# magicmouth-v1_0.net
KiCad netlist of a schematic drawn in EAGLE
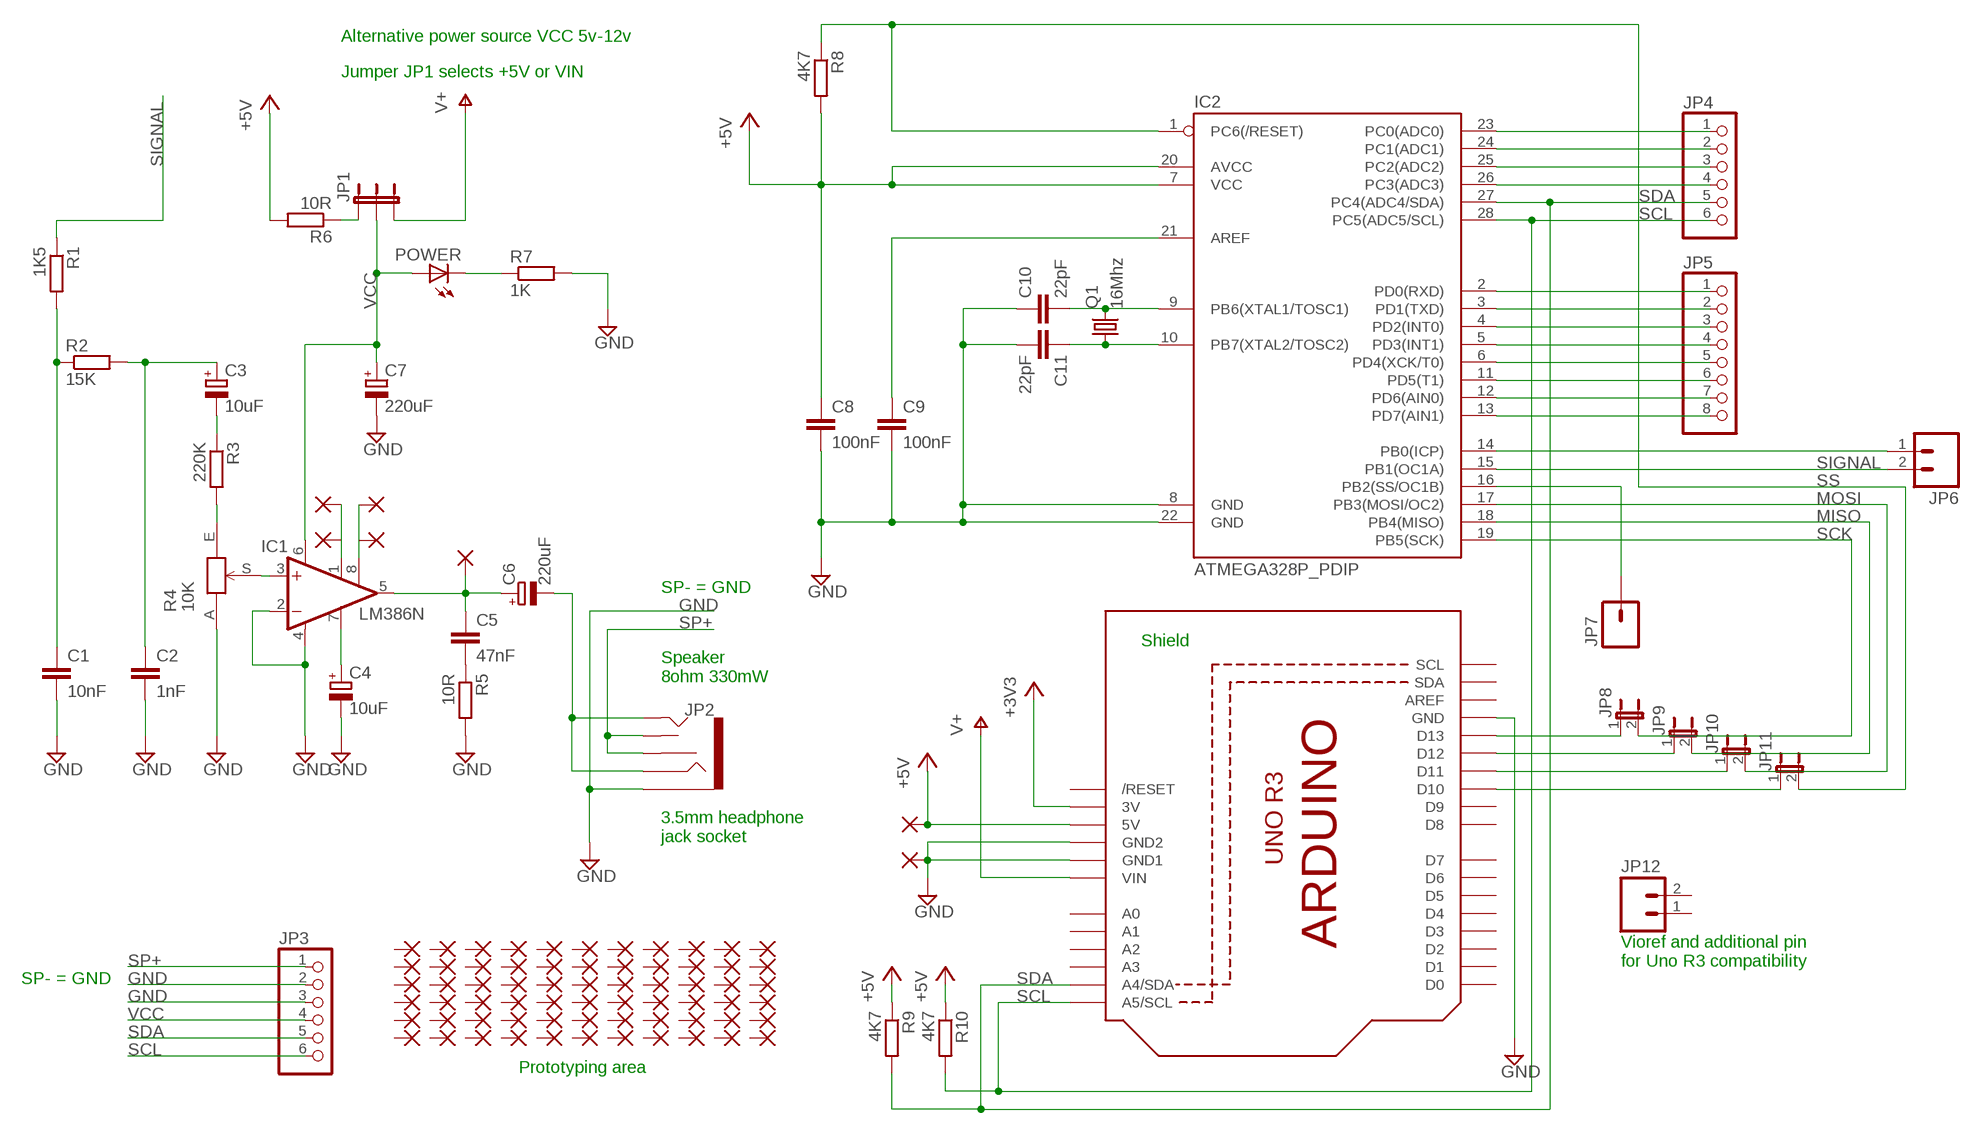
[diagram p0: schematic, sheet 1]

(export (version "E")
  (design (tool "Eeschema 10.0.6"))
  (components
    (comp (ref "C1")
      (value "10nF")
      (footprint "eagle-import:C050-025X075")
      (libsource (lib "eagle-import") (part "C-EU050-025X075"))
    )
    (comp (ref "C2")
      (value "1nF")
      (footprint "eagle-import:C050-025X075")
      (libsource (lib "eagle-import") (part "C-EU050-025X075"))
    )
    (comp (ref "C3")
      (value "10uF")
      (footprint "eagle-import:E2,5-7")
      (libsource (lib "eagle-import") (part "CPOL-EUE2.5-7"))
    )
    (comp (ref "C4")
      (value "10uF")
      (footprint "eagle-import:E2,5-7")
      (libsource (lib "eagle-import") (part "CPOL-EUE2.5-7"))
    )
    (comp (ref "C5")
      (value "47nF")
      (footprint "eagle-import:C050-025X075")
      (libsource (lib "eagle-import") (part "C-EU050-025X075"))
    )
    (comp (ref "C6")
      (value "220uF")
      (footprint "eagle-import:TT2D7")
      (libsource (lib "eagle-import") (part "CPOL-EUTT2D7"))
    )
    (comp (ref "C7")
      (value "220uF")
      (footprint "eagle-import:TT2D7")
      (libsource (lib "eagle-import") (part "CPOL-EUTT2D7"))
    )
    (comp (ref "C8")
      (value "100nF")
      (footprint "eagle-import:C025-025X050")
      (fields (field (name "CAPACITANCE") "10 nF"))
      (libsource (lib "eagle-import") (part "C-EU025-025X050"))
    )
    (comp (ref "C9")
      (value "100nF")
      (footprint "eagle-import:C025-025X050")
      (fields (field (name "CAPACITANCE") "100 nF"))
      (libsource (lib "eagle-import") (part "C-EU025-025X050"))
    )
    (comp (ref "C10")
      (value "22pF")
      (footprint "eagle-import:C025-025X050")
      (fields (field (name "CAPACITANCE") "22 pf"))
      (libsource (lib "eagle-import") (part "C-EU025-025X050"))
    )
    (comp (ref "C11")
      (value "22pF")
      (footprint "eagle-import:C025-025X050")
      (fields (field (name "CAPACITANCE") "22 pf"))
      (libsource (lib "eagle-import") (part "C-EU025-025X050"))
    )
    (comp (ref "IC1")
      (value "LM386N")
      (footprint "eagle-import:DIL08")
      (libsource (lib "eagle-import") (part "LM386?-N1"))
    )
    (comp (ref "IC2")
      (value "ATMEGA328P_PDIP")
      (footprint "eagle-import:DIL28-3")
      (libsource (lib "eagle-import") (part "ATMEGA328P_PDIP"))
    )
    (comp (ref "JP1")
      (value "JUMPER-3PTH")
      (footprint "eagle-import:1X03")
      (libsource (lib "eagle-import") (part "JUMPER-3PTH"))
    )
    (comp (ref "JP2")
      (value "AUDIO-JACK2PTH")
      (footprint "eagle-import:AUDIO-JACK")
      (libsource (lib "eagle-import") (part "AUDIO-JACK2PTH"))
    )
    (comp (ref "JP3")
      (value "PINHD-1X6CB")
      (footprint "eagle-import:1X06-CLEANBIG")
      (libsource (lib "eagle-import") (part "PINHD-1X6CB"))
    )
    (comp (ref "JP4")
      (value "PINHD-1X6CB")
      (footprint "eagle-import:1X06-CLEANBIG")
      (libsource (lib "eagle-import") (part "PINHD-1X6CB"))
    )
    (comp (ref "JP5")
      (value "PINHD-1X8CLEANBIG")
      (footprint "eagle-import:1X08-CLEANBIG")
      (libsource (lib "eagle-import") (part "PINHD-1X8CLEANBIG"))
    )
    (comp (ref "JP6")
      (value "M021X02_NO_SILK")
      (footprint "eagle-import:1X02_NO_SILK")
      (libsource (lib "eagle-import") (part "SparkFun-Connectors_M021X02_NO_SILK"))
    )
    (comp (ref "JP7")
      (value "M01SMDNS")
      (footprint "eagle-import:1X01NS")
      (libsource (lib "eagle-import") (part "M01SMDNS"))
    )
    (comp (ref "JP8")
      (value "JUMPER-2PTH")
      (footprint "eagle-import:1X02")
      (libsource (lib "eagle-import") (part "JUMPER-2PTH"))
    )
    (comp (ref "JP9")
      (value "JUMPER-2PTH")
      (footprint "eagle-import:1X02")
      (libsource (lib "eagle-import") (part "JUMPER-2PTH"))
    )
    (comp (ref "JP10")
      (value "JUMPER-2PTH")
      (footprint "eagle-import:1X02")
      (libsource (lib "eagle-import") (part "JUMPER-2PTH"))
    )
    (comp (ref "JP11")
      (value "JUMPER-2PTH")
      (footprint "eagle-import:1X02")
      (libsource (lib "eagle-import") (part "JUMPER-2PTH"))
    )
    (comp (ref "JP12")
      (value "M021X02_NO_SILK")
      (footprint "eagle-import:1X02_NO_SILK")
      (libsource (lib "eagle-import") (part "M021X02_NO_SILK"))
    )
    (comp (ref "P1")
      (value "1,6/0,8")
      (footprint "eagle-import:1,6_0,8")
      (libsource (lib "eagle-import") (part "1,6/0,8"))
    )
    (comp (ref "P5")
      (value "1,6/0,8")
      (footprint "eagle-import:1,6_0,8")
      (libsource (lib "eagle-import") (part "1,6/0,8"))
    )
    (comp (ref "P8")
      (value "1,6/0,8")
      (footprint "eagle-import:1,6_0,8")
      (libsource (lib "eagle-import") (part "1,6/0,8"))
    )
    (comp (ref "PAD1")
      (value "1,6/0,8")
      (footprint "eagle-import:1,6_0,8")
      (libsource (lib "eagle-import") (part "1,6/0,8"))
    )
    (comp (ref "PAD3")
      (value "1,6/0,8")
      (footprint "eagle-import:1,6_0,8")
      (libsource (lib "eagle-import") (part "1,6/0,8"))
    )
    (comp (ref "PAD7")
      (value "1,6/0,8")
      (footprint "eagle-import:1,6_0,8")
      (libsource (lib "eagle-import") (part "1,6/0,8"))
    )
    (comp (ref "PAD8")
      (value "1,6/0,8")
      (footprint "eagle-import:1,6_0,8")
      (libsource (lib "eagle-import") (part "1,6/0,8"))
    )
    (comp (ref "PAD9")
      (value "1,6/0,8")
      (footprint "eagle-import:1,6_0,8")
      (libsource (lib "eagle-import") (part "1,6/0,8"))
    )
    (comp (ref "PAD10")
      (value "1,6/0,8")
      (footprint "eagle-import:1,6_0,8")
      (libsource (lib "eagle-import") (part "1,6/0,8"))
    )
    (comp (ref "PAD11")
      (value "1,6/0,8")
      (footprint "eagle-import:1,6_0,8")
      (libsource (lib "eagle-import") (part "1,6/0,8"))
    )
    (comp (ref "PAD12")
      (value "1,6/0,8")
      (footprint "eagle-import:1,6_0,8")
      (libsource (lib "eagle-import") (part "1,6/0,8"))
    )
    (comp (ref "PAD13")
      (value "1,6/0,8")
      (footprint "eagle-import:1,6_0,8")
      (libsource (lib "eagle-import") (part "1,6/0,8"))
    )
    (comp (ref "PAD14")
      (value "1,6/0,8")
      (footprint "eagle-import:1,6_0,8")
      (libsource (lib "eagle-import") (part "1,6/0,8"))
    )
    (comp (ref "PAD15")
      (value "1,6/0,8")
      (footprint "eagle-import:1,6_0,8")
      (libsource (lib "eagle-import") (part "1,6/0,8"))
    )
    (comp (ref "PAD16")
      (value "1,6/0,8")
      (footprint "eagle-import:1,6_0,8")
      (libsource (lib "eagle-import") (part "1,6/0,8"))
    )
    (comp (ref "PAD17")
      (value "1,6/0,8")
      (footprint "eagle-import:1,6_0,8")
      (libsource (lib "eagle-import") (part "1,6/0,8"))
    )
    (comp (ref "PAD18")
      (value "1,6/0,8")
      (footprint "eagle-import:1,6_0,8")
      (libsource (lib "eagle-import") (part "1,6/0,8"))
    )
    (comp (ref "PAD19")
      (value "1,6/0,8")
      (footprint "eagle-import:1,6_0,8")
      (libsource (lib "eagle-import") (part "1,6/0,8"))
    )
    (comp (ref "PAD20")
      (value "1,6/0,8")
      (footprint "eagle-import:1,6_0,8")
      (libsource (lib "eagle-import") (part "1,6/0,8"))
    )
    (comp (ref "PAD21")
      (value "1,6/0,8")
      (footprint "eagle-import:1,6_0,8")
      (libsource (lib "eagle-import") (part "1,6/0,8"))
    )
    (comp (ref "PAD22")
      (value "1,6/0,8")
      (footprint "eagle-import:1,6_0,8")
      (libsource (lib "eagle-import") (part "1,6/0,8"))
    )
    (comp (ref "PAD23")
      (value "1,6/0,8")
      (footprint "eagle-import:1,6_0,8")
      (libsource (lib "eagle-import") (part "1,6/0,8"))
    )
    (comp (ref "PAD24")
      (value "1,6/0,8")
      (footprint "eagle-import:1,6_0,8")
      (libsource (lib "eagle-import") (part "1,6/0,8"))
    )
    (comp (ref "PAD25")
      (value "1,6/0,8")
      (footprint "eagle-import:1,6_0,8")
      (libsource (lib "eagle-import") (part "1,6/0,8"))
    )
    (comp (ref "PAD26")
      (value "1,6/0,8")
      (footprint "eagle-import:1,6_0,8")
      (libsource (lib "eagle-import") (part "1,6/0,8"))
    )
    (comp (ref "PAD27")
      (value "1,6/0,8")
      (footprint "eagle-import:1,6_0,8")
      (libsource (lib "eagle-import") (part "1,6/0,8"))
    )
    (comp (ref "PAD28")
      (value "1,6/0,8")
      (footprint "eagle-import:1,6_0,8")
      (libsource (lib "eagle-import") (part "1,6/0,8"))
    )
    (comp (ref "PAD29")
      (value "1,6/0,8")
      (footprint "eagle-import:1,6_0,8")
      (libsource (lib "eagle-import") (part "1,6/0,8"))
    )
    (comp (ref "PAD30")
      (value "1,6/0,8")
      (footprint "eagle-import:1,6_0,8")
      (libsource (lib "eagle-import") (part "1,6/0,8"))
    )
    (comp (ref "PAD31")
      (value "1,6/0,8")
      (footprint "eagle-import:1,6_0,8")
      (libsource (lib "eagle-import") (part "1,6/0,8"))
    )
    (comp (ref "PAD32")
      (value "1,6/0,8")
      (footprint "eagle-import:1,6_0,8")
      (libsource (lib "eagle-import") (part "1,6/0,8"))
    )
    (comp (ref "PAD33")
      (value "1,6/0,8")
      (footprint "eagle-import:1,6_0,8")
      (libsource (lib "eagle-import") (part "1,6/0,8"))
    )
    (comp (ref "PAD34")
      (value "1,6/0,8")
      (footprint "eagle-import:1,6_0,8")
      (libsource (lib "eagle-import") (part "1,6/0,8"))
    )
    (comp (ref "PAD35")
      (value "1,6/0,8")
      (footprint "eagle-import:1,6_0,8")
      (libsource (lib "eagle-import") (part "1,6/0,8"))
    )
    (comp (ref "PAD36")
      (value "1,6/0,8")
      (footprint "eagle-import:1,6_0,8")
      (libsource (lib "eagle-import") (part "1,6/0,8"))
    )
    (comp (ref "PAD37")
      (value "1,6/0,8")
      (footprint "eagle-import:1,6_0,8")
      (libsource (lib "eagle-import") (part "1,6/0,8"))
    )
    (comp (ref "PAD38")
      (value "1,6/0,8")
      (footprint "eagle-import:1,6_0,8")
      (libsource (lib "eagle-import") (part "1,6/0,8"))
    )
    (comp (ref "PAD39")
      (value "1,6/0,8")
      (footprint "eagle-import:1,6_0,8")
      (libsource (lib "eagle-import") (part "1,6/0,8"))
    )
    (comp (ref "PAD40")
      (value "1,6/0,8")
      (footprint "eagle-import:1,6_0,8")
      (libsource (lib "eagle-import") (part "1,6/0,8"))
    )
    (comp (ref "PAD41")
      (value "1,6/0,8")
      (footprint "eagle-import:1,6_0,8")
      (libsource (lib "eagle-import") (part "1,6/0,8"))
    )
    (comp (ref "PAD42")
      (value "1,6/0,8")
      (footprint "eagle-import:1,6_0,8")
      (libsource (lib "eagle-import") (part "1,6/0,8"))
    )
    (comp (ref "PAD43")
      (value "1,6/0,8")
      (footprint "eagle-import:1,6_0,8")
      (libsource (lib "eagle-import") (part "1,6/0,8"))
    )
    (comp (ref "PAD44")
      (value "1,6/0,8")
      (footprint "eagle-import:1,6_0,8")
      (libsource (lib "eagle-import") (part "1,6/0,8"))
    )
    (comp (ref "PAD45")
      (value "1,6/0,8")
      (footprint "eagle-import:1,6_0,8")
      (libsource (lib "eagle-import") (part "1,6/0,8"))
    )
    (comp (ref "PAD46")
      (value "1,6/0,8")
      (footprint "eagle-import:1,6_0,8")
      (libsource (lib "eagle-import") (part "1,6/0,8"))
    )
    (comp (ref "PAD47")
      (value "1,6/0,8")
      (footprint "eagle-import:1,6_0,8")
      (libsource (lib "eagle-import") (part "1,6/0,8"))
    )
    (comp (ref "PAD48")
      (value "1,6/0,8")
      (footprint "eagle-import:1,6_0,8")
      (libsource (lib "eagle-import") (part "1,6/0,8"))
    )
    (comp (ref "PAD49")
      (value "1,6/0,8")
      (footprint "eagle-import:1,6_0,8")
      (libsource (lib "eagle-import") (part "1,6/0,8"))
    )
    (comp (ref "PAD50")
      (value "1,6/0,8")
      (footprint "eagle-import:1,6_0,8")
      (libsource (lib "eagle-import") (part "1,6/0,8"))
    )
    (comp (ref "PAD51")
      (value "1,6/0,8")
      (footprint "eagle-import:1,6_0,8")
      (libsource (lib "eagle-import") (part "1,6/0,8"))
    )
    (comp (ref "PAD52")
      (value "1,6/0,8")
      (footprint "eagle-import:1,6_0,8")
      (libsource (lib "eagle-import") (part "1,6/0,8"))
    )
    (comp (ref "PAD53")
      (value "1,6/0,8")
      (footprint "eagle-import:1,6_0,8")
      (libsource (lib "eagle-import") (part "1,6/0,8"))
    )
    (comp (ref "PAD54")
      (value "1,6/0,8")
      (footprint "eagle-import:1,6_0,8")
      (libsource (lib "eagle-import") (part "1,6/0,8"))
    )
    (comp (ref "PAD55")
      (value "1,6/0,8")
      (footprint "eagle-import:1,6_0,8")
      (libsource (lib "eagle-import") (part "1,6/0,8"))
    )
    (comp (ref "PAD56")
      (value "1,6/0,8")
      (footprint "eagle-import:1,6_0,8")
      (libsource (lib "eagle-import") (part "1,6/0,8"))
    )
    (comp (ref "PAD57")
      (value "1,6/0,8")
      (footprint "eagle-import:1,6_0,8")
      (libsource (lib "eagle-import") (part "1,6/0,8"))
    )
    (comp (ref "PAD58")
      (value "1,6/0,8")
      (footprint "eagle-import:1,6_0,8")
      (libsource (lib "eagle-import") (part "1,6/0,8"))
    )
    (comp (ref "PAD59")
      (value "1,6/0,8")
      (footprint "eagle-import:1,6_0,8")
      (libsource (lib "eagle-import") (part "1,6/0,8"))
    )
    (comp (ref "PAD60")
      (value "1,6/0,8")
      (footprint "eagle-import:1,6_0,8")
      (libsource (lib "eagle-import") (part "1,6/0,8"))
    )
    (comp (ref "PAD61")
      (value "1,6/0,8")
      (footprint "eagle-import:1,6_0,8")
      (libsource (lib "eagle-import") (part "1,6/0,8"))
    )
    (comp (ref "PAD62")
      (value "1,6/0,8")
      (footprint "eagle-import:1,6_0,8")
      (libsource (lib "eagle-import") (part "1,6/0,8"))
    )
    (comp (ref "PAD63")
      (value "1,6/0,8")
      (footprint "eagle-import:1,6_0,8")
      (libsource (lib "eagle-import") (part "1,6/0,8"))
    )
    (comp (ref "PAD64")
      (value "1,6/0,8")
      (footprint "eagle-import:1,6_0,8")
      (libsource (lib "eagle-import") (part "1,6/0,8"))
    )
    (comp (ref "PAD65")
      (value "1,6/0,8")
      (footprint "eagle-import:1,6_0,8")
      (libsource (lib "eagle-import") (part "1,6/0,8"))
    )
    (comp (ref "PAD66")
      (value "1,6/0,8")
      (footprint "eagle-import:1,6_0,8")
      (libsource (lib "eagle-import") (part "1,6/0,8"))
    )
    (comp (ref "PAD67")
      (value "1,6/0,8")
      (footprint "eagle-import:1,6_0,8")
      (libsource (lib "eagle-import") (part "1,6/0,8"))
    )
    (comp (ref "PAD68")
      (value "1,6/0,8")
      (footprint "eagle-import:1,6_0,8")
      (libsource (lib "eagle-import") (part "1,6/0,8"))
    )
    (comp (ref "PAD69")
      (value "1,6/0,8")
      (footprint "eagle-import:1,6_0,8")
      (libsource (lib "eagle-import") (part "1,6/0,8"))
    )
    (comp (ref "PAD70")
      (value "1,6/0,8")
      (footprint "eagle-import:1,6_0,8")
      (libsource (lib "eagle-import") (part "1,6/0,8"))
    )
    (comp (ref "PAD71")
      (value "1,6/0,8")
      (footprint "eagle-import:1,6_0,8")
      (libsource (lib "eagle-import") (part "1,6/0,8"))
    )
    (comp (ref "PAD72")
      (value "1,6/0,8")
      (footprint "eagle-import:1,6_0,8")
      (libsource (lib "eagle-import") (part "1,6/0,8"))
    )
    (comp (ref "PAD73")
      (value "1,6/0,8")
      (footprint "eagle-import:1,6_0,8")
      (libsource (lib "eagle-import") (part "1,6/0,8"))
    )
    (comp (ref "PAD74")
      (value "1,6/0,8")
      (footprint "eagle-import:1,6_0,8")
      (libsource (lib "eagle-import") (part "1,6/0,8"))
    )
    (comp (ref "POWER")
      (value "LED3MM")
      (footprint "eagle-import:LED3MM")
      (libsource (lib "eagle-import") (part "LED3MM"))
    )
    (comp (ref "Q1")
      (value "16Mhz")
      (footprint "eagle-import:HC49_S")
      (libsource (lib "eagle-import") (part "CRYSTALHC49S"))
    )
    (comp (ref "R1")
      (value "1K5")
      (footprint "eagle-import:0207_7")
      (libsource (lib "eagle-import") (part "R-EU_0207/7"))
    )
    (comp (ref "R2")
      (value "15K")
      (footprint "eagle-import:0207_7")
      (libsource (lib "eagle-import") (part "R-EU_0207/7"))
    )
    (comp (ref "R3")
      (value "220K")
      (footprint "eagle-import:0207_7")
      (libsource (lib "eagle-import") (part "resistor_R-EU_0207/7"))
    )
    (comp (ref "R4")
      (value "10K")
      (footprint "eagle-import:3352T")
      (libsource (lib "eagle-import") (part "TPOT3352"))
    )
    (comp (ref "R5")
      (value "10R")
      (footprint "eagle-import:0207_7")
      (libsource (lib "eagle-import") (part "resistor_R-EU_0207/7"))
    )
    (comp (ref "R6")
      (value "10R")
      (footprint "eagle-import:0207_7")
      (libsource (lib "eagle-import") (part "R-EU_0207/7"))
    )
    (comp (ref "R7")
      (value "1K")
      (footprint "eagle-import:0207_7")
      (libsource (lib "eagle-import") (part "R-EU_0207/7"))
    )
    (comp (ref "R8")
      (value "4K7")
      (footprint "eagle-import:0207_7")
      (fields (field (name "RESISTANCE") "4K7"))
      (libsource (lib "eagle-import") (part "R-EU_0207/7"))
    )
    (comp (ref "R9")
      (value "4K7")
      (footprint "eagle-import:0207_7")
      (fields (field (name "RESISTANCE") "4K7"))
      (libsource (lib "eagle-import") (part "R-EU_0207/7"))
    )
    (comp (ref "R10")
      (value "4K7")
      (footprint "eagle-import:0207_7")
      (fields (field (name "RESISTANCE") "4K7"))
      (libsource (lib "eagle-import") (part "R-EU_0207/7"))
    )
    (comp (ref "U1")
      (value "ARDUINOR3-NOIOREF-NOTEXT")
      (footprint "eagle-import:ARDUINOR3-NOTEXT-NOIOREF")
      (libsource (lib "eagle-import") (part "ARDUINOR3-NOIOREF-NOTEXT"))
    )
  )
  (nets
    (net (code "1") (name "+3V3") (class "Default")
      (node (ref "U1") (pin "3V") (pinfunction "3V_3V") (pintype "power_in"))
    )
    (net (code "2") (name "+5V") (class "Default")
      (node (ref "C8") (pin "1") (pinfunction "1_1") (pintype "passive"))
      (node (ref "IC2") (pin "20") (pinfunction "AVCC_20") (pintype "bidirectional"))
      (node (ref "IC2") (pin "7") (pinfunction "VCC_7") (pintype "bidirectional"))
      (node (ref "PAD55") (pin "1") (pinfunction "P_1") (pintype "passive"))
      (node (ref "R10") (pin "1") (pinfunction "1_1") (pintype "passive"))
      (node (ref "R6") (pin "2") (pinfunction "2_2") (pintype "passive"))
      (node (ref "R8") (pin "2") (pinfunction "2_2") (pintype "passive"))
      (node (ref "R9") (pin "1") (pinfunction "1_1") (pintype "passive"))
      (node (ref "U1") (pin "5V") (pinfunction "5V_5V") (pintype "power_in"))
    )
    (net (code "3") (name "/MISO") (class "Default")
      (node (ref "IC2") (pin "18") (pinfunction "PB4(MISO)_18") (pintype "bidirectional"))
      (node (ref "JP9") (pin "2") (pinfunction "2_2") (pintype "passive"))
    )
    (net (code "4") (name "/MOSI") (class "Default")
      (node (ref "IC2") (pin "17") (pinfunction "PB3(MOSI/OC2)_17") (pintype "bidirectional"))
      (node (ref "JP10") (pin "2") (pinfunction "2_2") (pintype "passive"))
    )
    (net (code "5") (name "/SCK") (class "Default")
      (node (ref "IC2") (pin "19") (pinfunction "PB5(SCK)_19") (pintype "bidirectional"))
      (node (ref "JP8") (pin "2") (pinfunction "2_2") (pintype "passive"))
    )
    (net (code "6") (name "/SCL") (class "Default")
      (node (ref "IC2") (pin "28") (pinfunction "PC5(ADC5/SCL)_28") (pintype "bidirectional"))
      (node (ref "JP3") (pin "6") (pinfunction "6_6") (pintype "passive"))
      (node (ref "JP4") (pin "6") (pinfunction "6_6") (pintype "passive"))
      (node (ref "R10") (pin "2") (pinfunction "2_2") (pintype "passive"))
      (node (ref "U1") (pin "A5") (pinfunction "A5/SCL_A5") (pintype "bidirectional"))
    )
    (net (code "7") (name "/SDA") (class "Default")
      (node (ref "IC2") (pin "27") (pinfunction "PC4(ADC4/SDA)_27") (pintype "bidirectional"))
      (node (ref "JP3") (pin "5") (pinfunction "5_5") (pintype "passive"))
      (node (ref "JP4") (pin "5") (pinfunction "5_5") (pintype "passive"))
      (node (ref "R9") (pin "2") (pinfunction "2_2") (pintype "passive"))
      (node (ref "U1") (pin "A4") (pinfunction "A4/SDA_A4") (pintype "bidirectional"))
    )
    (net (code "8") (name "/SIGNAL") (class "Default")
      (node (ref "IC2") (pin "15") (pinfunction "PB1(OC1A)_15") (pintype "bidirectional"))
      (node (ref "JP6") (pin "2") (pinfunction "2_2") (pintype "passive"))
      (node (ref "R1") (pin "1") (pinfunction "1_1") (pintype "passive"))
    )
    (net (code "9") (name "/SP+") (class "Default")
      (node (ref "JP2") (pin "RSH") (pinfunction "RSH_RSH") (pintype "bidirectional"))
      (node (ref "JP2") (pin "TSH") (pinfunction "TSH_TSH") (pintype "bidirectional"))
      (node (ref "JP3") (pin "1") (pinfunction "1_1") (pintype "passive"))
    )
    (net (code "10") (name "/SS") (class "Default")
      (node (ref "IC2") (pin "1") (pinfunction "PC6(/RESET)_1") (pintype "bidirectional"))
      (node (ref "JP11") (pin "2") (pinfunction "2_2") (pintype "passive"))
      (node (ref "R8") (pin "1") (pinfunction "1_1") (pintype "passive"))
    )
    (net (code "11") (name "/VCC") (class "Default")
      (node (ref "C7") (pin "+") (pinfunction "+_+") (pintype "passive"))
      (node (ref "IC1") (pin "6") (pinfunction "VS_6") (pintype "power_in"))
      (node (ref "JP1") (pin "2") (pinfunction "2_2") (pintype "passive"))
      (node (ref "JP3") (pin "4") (pinfunction "4_4") (pintype "passive"))
      (node (ref "POWER") (pin "A") (pinfunction "A_A") (pintype "passive"))
    )
    (net (code "12") (name "GND") (class "Default")
      (node (ref "C1") (pin "2") (pinfunction "2_2") (pintype "passive"))
      (node (ref "C10") (pin "1") (pinfunction "1_1") (pintype "passive"))
      (node (ref "C11") (pin "2") (pinfunction "2_2") (pintype "passive"))
      (node (ref "C2") (pin "2") (pinfunction "2_2") (pintype "passive"))
      (node (ref "C4") (pin "-") (pinfunction "-_-") (pintype "passive"))
      (node (ref "C7") (pin "-") (pinfunction "-_-") (pintype "passive"))
      (node (ref "C8") (pin "2") (pinfunction "2_2") (pintype "passive"))
      (node (ref "C9") (pin "2") (pinfunction "2_2") (pintype "passive"))
      (node (ref "IC1") (pin "2") (pinfunction "-IN_2") (pintype "input"))
      (node (ref "IC1") (pin "4") (pinfunction "GND_4") (pintype "power_in"))
      (node (ref "IC2") (pin "22") (pinfunction "GND_22") (pintype "bidirectional"))
      (node (ref "IC2") (pin "8") (pinfunction "GND_8") (pintype "bidirectional"))
      (node (ref "JP2") (pin "SLEEVE") (pinfunction "SLEEVE_SLEEVE") (pintype "bidirectional"))
      (node (ref "JP3") (pin "2") (pinfunction "2_2") (pintype "passive"))
      (node (ref "JP3") (pin "3") (pinfunction "3_3") (pintype "passive"))
      (node (ref "PAD68") (pin "1") (pinfunction "P_1") (pintype "passive"))
      (node (ref "R4") (pin "A") (pinfunction "A_A") (pintype "passive"))
      (node (ref "R5") (pin "2") (pinfunction "2_2") (pintype "passive"))
      (node (ref "R7") (pin "2") (pinfunction "2_2") (pintype "passive"))
      (node (ref "U1") (pin "GND") (pinfunction "GND_GND") (pintype "power_in"))
      (node (ref "U1") (pin "GND1") (pinfunction "GND1_GND1") (pintype "power_in"))
      (node (ref "U1") (pin "GND2") (pinfunction "GND2_GND2") (pintype "power_in"))
    )
    (net (code "13") (name "Net-(C1-Pad1)") (class "Default")
      (node (ref "C1") (pin "1") (pinfunction "1_1") (pintype "passive"))
      (node (ref "R1") (pin "2") (pinfunction "2_2") (pintype "passive"))
      (node (ref "R2") (pin "1") (pinfunction "1_1") (pintype "passive"))
    )
    (net (code "14") (name "Net-(C2-Pad1)") (class "Default")
      (node (ref "C2") (pin "1") (pinfunction "1_1") (pintype "passive"))
      (node (ref "C3") (pin "+") (pinfunction "+_+") (pintype "passive"))
      (node (ref "R2") (pin "2") (pinfunction "2_2") (pintype "passive"))
    )
    (net (code "15") (name "Net-(C3-Pad-)") (class "Default")
      (node (ref "C3") (pin "-") (pinfunction "-_-") (pintype "passive"))
      (node (ref "R3") (pin "1") (pinfunction "1_1") (pintype "passive"))
    )
    (net (code "16") (name "Net-(C5-Pad2)") (class "Default")
      (node (ref "C5") (pin "2") (pinfunction "2_2") (pintype "passive"))
      (node (ref "R5") (pin "1") (pinfunction "1_1") (pintype "passive"))
    )
    (net (code "17") (name "Net-(C6-Pad-)") (class "Default")
      (node (ref "C6") (pin "-") (pinfunction "-_-") (pintype "passive"))
      (node (ref "JP2") (pin "RING") (pinfunction "RING_RING") (pintype "bidirectional"))
      (node (ref "JP2") (pin "TIP") (pinfunction "TIP_TIP") (pintype "bidirectional"))
    )
    (net (code "18") (name "Net-(IC1-+IN)") (class "Default")
      (node (ref "IC1") (pin "3") (pinfunction "+IN_3") (pintype "input"))
      (node (ref "R4") (pin "S") (pinfunction "S_S") (pintype "passive"))
    )
    (net (code "19") (name "Net-(IC1-BYPASS)") (class "Default")
      (node (ref "C4") (pin "+") (pinfunction "+_+") (pintype "passive"))
      (node (ref "IC1") (pin "7") (pinfunction "BYPASS_7") (pintype "passive"))
    )
    (net (code "20") (name "Net-(IC1-OUT)") (class "Default")
      (node (ref "C5") (pin "1") (pinfunction "1_1") (pintype "passive"))
      (node (ref "C6") (pin "+") (pinfunction "+_+") (pintype "passive"))
      (node (ref "IC1") (pin "5") (pinfunction "OUT_5") (pintype "output"))
      (node (ref "P5") (pin "1") (pinfunction "P_1") (pintype "passive"))
    )
    (net (code "21") (name "Net-(IC2-AREF)") (class "Default")
      (node (ref "C9") (pin "1") (pinfunction "1_1") (pintype "passive"))
      (node (ref "IC2") (pin "21") (pinfunction "AREF_21") (pintype "bidirectional"))
    )
    (net (code "22") (name "Net-(IC2-PB0(ICP))") (class "Default")
      (node (ref "IC2") (pin "14") (pinfunction "PB0(ICP)_14") (pintype "bidirectional"))
      (node (ref "JP6") (pin "1") (pinfunction "1_1") (pintype "passive"))
    )
    (net (code "23") (name "Net-(IC2-PB2(SS{slash}OC1B))") (class "Default")
      (node (ref "IC2") (pin "16") (pinfunction "PB2(SS/OC1B)_16") (pintype "bidirectional"))
      (node (ref "JP7") (pin "1") (pinfunction "1_1") (pintype "passive"))
    )
    (net (code "24") (name "Net-(IC2-PB6(XTAL1{slash}TOSC1))") (class "Default")
      (node (ref "C10") (pin "2") (pinfunction "2_2") (pintype "passive"))
      (node (ref "IC2") (pin "9") (pinfunction "PB6(XTAL1/TOSC1)_9") (pintype "bidirectional"))
      (node (ref "Q1") (pin "2") (pinfunction "2_2") (pintype "passive"))
    )
    (net (code "25") (name "Net-(IC2-PB7(XTAL2{slash}TOSC2))") (class "Default")
      (node (ref "C11") (pin "1") (pinfunction "1_1") (pintype "passive"))
      (node (ref "IC2") (pin "10") (pinfunction "PB7(XTAL2/TOSC2)_10") (pintype "bidirectional"))
      (node (ref "Q1") (pin "1") (pinfunction "1_1") (pintype "passive"))
    )
    (net (code "26") (name "Net-(IC2-PC0(ADC0))") (class "Default")
      (node (ref "IC2") (pin "23") (pinfunction "PC0(ADC0)_23") (pintype "bidirectional"))
      (node (ref "JP4") (pin "1") (pinfunction "1_1") (pintype "passive"))
    )
    (net (code "27") (name "Net-(IC2-PC1(ADC1))") (class "Default")
      (node (ref "IC2") (pin "24") (pinfunction "PC1(ADC1)_24") (pintype "bidirectional"))
      (node (ref "JP4") (pin "2") (pinfunction "2_2") (pintype "passive"))
    )
    (net (code "28") (name "Net-(IC2-PC2(ADC2))") (class "Default")
      (node (ref "IC2") (pin "25") (pinfunction "PC2(ADC2)_25") (pintype "bidirectional"))
      (node (ref "JP4") (pin "3") (pinfunction "3_3") (pintype "passive"))
    )
    (net (code "29") (name "Net-(IC2-PC3(ADC3))") (class "Default")
      (node (ref "IC2") (pin "26") (pinfunction "PC3(ADC3)_26") (pintype "bidirectional"))
      (node (ref "JP4") (pin "4") (pinfunction "4_4") (pintype "passive"))
    )
    (net (code "30") (name "Net-(IC2-PD0(RXD))") (class "Default")
      (node (ref "IC2") (pin "2") (pinfunction "PD0(RXD)_2") (pintype "bidirectional"))
      (node (ref "JP5") (pin "1") (pinfunction "1_1") (pintype "passive"))
    )
    (net (code "31") (name "Net-(IC2-PD1(TXD))") (class "Default")
      (node (ref "IC2") (pin "3") (pinfunction "PD1(TXD)_3") (pintype "bidirectional"))
      (node (ref "JP5") (pin "2") (pinfunction "2_2") (pintype "passive"))
    )
    (net (code "32") (name "Net-(IC2-PD2(INT0))") (class "Default")
      (node (ref "IC2") (pin "4") (pinfunction "PD2(INT0)_4") (pintype "bidirectional"))
      (node (ref "JP5") (pin "3") (pinfunction "3_3") (pintype "passive"))
    )
    (net (code "33") (name "Net-(IC2-PD3(INT1))") (class "Default")
      (node (ref "IC2") (pin "5") (pinfunction "PD3(INT1)_5") (pintype "bidirectional"))
      (node (ref "JP5") (pin "4") (pinfunction "4_4") (pintype "passive"))
    )
    (net (code "34") (name "Net-(IC2-PD4(XCK{slash}T0))") (class "Default")
      (node (ref "IC2") (pin "6") (pinfunction "PD4(XCK/T0)_6") (pintype "bidirectional"))
      (node (ref "JP5") (pin "5") (pinfunction "5_5") (pintype "passive"))
    )
    (net (code "35") (name "Net-(IC2-PD5(T1))") (class "Default")
      (node (ref "IC2") (pin "11") (pinfunction "PD5(T1)_11") (pintype "bidirectional"))
      (node (ref "JP5") (pin "6") (pinfunction "6_6") (pintype "passive"))
    )
    (net (code "36") (name "Net-(IC2-PD6(AIN0))") (class "Default")
      (node (ref "IC2") (pin "12") (pinfunction "PD6(AIN0)_12") (pintype "bidirectional"))
      (node (ref "JP5") (pin "7") (pinfunction "7_7") (pintype "passive"))
    )
    (net (code "37") (name "Net-(IC2-PD7(AIN1))") (class "Default")
      (node (ref "IC2") (pin "13") (pinfunction "PD7(AIN1)_13") (pintype "bidirectional"))
      (node (ref "JP5") (pin "8") (pinfunction "8_8") (pintype "passive"))
    )
    (net (code "38") (name "Net-(JP1-Pad1)") (class "Default")
      (node (ref "JP1") (pin "1") (pinfunction "1_1") (pintype "passive"))
      (node (ref "R6") (pin "1") (pinfunction "1_1") (pintype "passive"))
    )
    (net (code "39") (name "Net-(JP8-Pad1)") (class "Default")
      (node (ref "JP8") (pin "1") (pinfunction "1_1") (pintype "passive"))
      (node (ref "U1") (pin "D13") (pinfunction "D13_D13") (pintype "bidirectional"))
    )
    (net (code "40") (name "Net-(JP9-Pad1)") (class "Default")
      (node (ref "JP9") (pin "1") (pinfunction "1_1") (pintype "passive"))
      (node (ref "U1") (pin "D12") (pinfunction "D12_D12") (pintype "bidirectional"))
    )
    (net (code "41") (name "Net-(JP10-Pad1)") (class "Default")
      (node (ref "JP10") (pin "1") (pinfunction "1_1") (pintype "passive"))
      (node (ref "U1") (pin "D11") (pinfunction "D11_D11") (pintype "bidirectional"))
    )
    (net (code "42") (name "Net-(JP11-Pad1)") (class "Default")
      (node (ref "JP11") (pin "1") (pinfunction "1_1") (pintype "passive"))
      (node (ref "U1") (pin "D10") (pinfunction "D10_D10") (pintype "bidirectional"))
    )
    (net (code "43") (name "Net-(P1-P)") (class "Default")
      (node (ref "IC1") (pin "1") (pinfunction "GAIN_1") (pintype "passive"))
      (node (ref "P1") (pin "1") (pinfunction "P_1") (pintype "passive"))
      (node (ref "PAD1") (pin "1") (pinfunction "P_1") (pintype "passive"))
    )
    (net (code "44") (name "Net-(P8-P)") (class "Default")
      (node (ref "IC1") (pin "8") (pinfunction "GAIN_8") (pintype "passive"))
      (node (ref "P8") (pin "1") (pinfunction "P_1") (pintype "passive"))
      (node (ref "PAD3") (pin "1") (pinfunction "P_1") (pintype "passive"))
    )
    (net (code "45") (name "Net-(POWER-C)") (class "Default")
      (node (ref "POWER") (pin "K") (pinfunction "C_K") (pintype "passive"))
      (node (ref "R7") (pin "1") (pinfunction "1_1") (pintype "passive"))
    )
    (net (code "46") (name "Net-(R3-Pad2)") (class "Default")
      (node (ref "R3") (pin "2") (pinfunction "2_2") (pintype "passive"))
      (node (ref "R4") (pin "E") (pinfunction "E_E") (pintype "passive"))
    )
    (net (code "47") (name "V+") (class "Default")
      (node (ref "JP1") (pin "3") (pinfunction "3_3") (pintype "passive"))
      (node (ref "U1") (pin "VIN") (pinfunction "VIN_VIN") (pintype "power_in"))
    )
    (net (code "48") (name "unconnected-(JP12-Pad1)") (class "Default")
      (node (ref "JP12") (pin "1") (pinfunction "1_1") (pintype "passive"))
    )
    (net (code "49") (name "unconnected-(JP12-Pad2)") (class "Default")
      (node (ref "JP12") (pin "2") (pinfunction "2_2") (pintype "passive"))
    )
    (net (code "50") (name "unconnected-(PAD7-P-Pad1)") (class "Default")
      (node (ref "PAD7") (pin "1") (pinfunction "P_1") (pintype "passive"))
    )
    (net (code "51") (name "unconnected-(PAD8-P-Pad1)") (class "Default")
      (node (ref "PAD8") (pin "1") (pinfunction "P_1") (pintype "passive"))
    )
    (net (code "52") (name "unconnected-(PAD9-P-Pad1)") (class "Default")
      (node (ref "PAD9") (pin "1") (pinfunction "P_1") (pintype "passive"))
    )
    (net (code "53") (name "unconnected-(PAD10-P-Pad1)") (class "Default")
      (node (ref "PAD10") (pin "1") (pinfunction "P_1") (pintype "passive"))
    )
    (net (code "54") (name "unconnected-(PAD11-P-Pad1)") (class "Default")
      (node (ref "PAD11") (pin "1") (pinfunction "P_1") (pintype "passive"))
    )
    (net (code "55") (name "unconnected-(PAD12-P-Pad1)") (class "Default")
      (node (ref "PAD12") (pin "1") (pinfunction "P_1") (pintype "passive"))
    )
    (net (code "56") (name "unconnected-(PAD13-P-Pad1)") (class "Default")
      (node (ref "PAD13") (pin "1") (pinfunction "P_1") (pintype "passive"))
    )
    (net (code "57") (name "unconnected-(PAD14-P-Pad1)") (class "Default")
      (node (ref "PAD14") (pin "1") (pinfunction "P_1") (pintype "passive"))
    )
    (net (code "58") (name "unconnected-(PAD15-P-Pad1)") (class "Default")
      (node (ref "PAD15") (pin "1") (pinfunction "P_1") (pintype "passive"))
    )
    (net (code "59") (name "unconnected-(PAD16-P-Pad1)") (class "Default")
      (node (ref "PAD16") (pin "1") (pinfunction "P_1") (pintype "passive"))
    )
    (net (code "60") (name "unconnected-(PAD17-P-Pad1)") (class "Default")
      (node (ref "PAD17") (pin "1") (pinfunction "P_1") (pintype "passive"))
    )
    (net (code "61") (name "unconnected-(PAD18-P-Pad1)") (class "Default")
      (node (ref "PAD18") (pin "1") (pinfunction "P_1") (pintype "passive"))
    )
    (net (code "62") (name "unconnected-(PAD19-P-Pad1)") (class "Default")
      (node (ref "PAD19") (pin "1") (pinfunction "P_1") (pintype "passive"))
    )
    (net (code "63") (name "unconnected-(PAD20-P-Pad1)") (class "Default")
      (node (ref "PAD20") (pin "1") (pinfunction "P_1") (pintype "passive"))
    )
    (net (code "64") (name "unconnected-(PAD21-P-Pad1)") (class "Default")
      (node (ref "PAD21") (pin "1") (pinfunction "P_1") (pintype "passive"))
    )
    (net (code "65") (name "unconnected-(PAD22-P-Pad1)") (class "Default")
      (node (ref "PAD22") (pin "1") (pinfunction "P_1") (pintype "passive"))
    )
    (net (code "66") (name "unconnected-(PAD23-P-Pad1)") (class "Default")
      (node (ref "PAD23") (pin "1") (pinfunction "P_1") (pintype "passive"))
    )
    (net (code "67") (name "unconnected-(PAD24-P-Pad1)") (class "Default")
      (node (ref "PAD24") (pin "1") (pinfunction "P_1") (pintype "passive"))
    )
    (net (code "68") (name "unconnected-(PAD25-P-Pad1)") (class "Default")
      (node (ref "PAD25") (pin "1") (pinfunction "P_1") (pintype "passive"))
    )
    (net (code "69") (name "unconnected-(PAD26-P-Pad1)") (class "Default")
      (node (ref "PAD26") (pin "1") (pinfunction "P_1") (pintype "passive"))
    )
    (net (code "70") (name "unconnected-(PAD27-P-Pad1)") (class "Default")
      (node (ref "PAD27") (pin "1") (pinfunction "P_1") (pintype "passive"))
    )
    (net (code "71") (name "unconnected-(PAD28-P-Pad1)") (class "Default")
      (node (ref "PAD28") (pin "1") (pinfunction "P_1") (pintype "passive"))
    )
    (net (code "72") (name "unconnected-(PAD29-P-Pad1)") (class "Default")
      (node (ref "PAD29") (pin "1") (pinfunction "P_1") (pintype "passive"))
    )
    (net (code "73") (name "unconnected-(PAD30-P-Pad1)") (class "Default")
      (node (ref "PAD30") (pin "1") (pinfunction "P_1") (pintype "passive"))
    )
    (net (code "74") (name "unconnected-(PAD31-P-Pad1)") (class "Default")
      (node (ref "PAD31") (pin "1") (pinfunction "P_1") (pintype "passive"))
    )
    (net (code "75") (name "unconnected-(PAD32-P-Pad1)") (class "Default")
      (node (ref "PAD32") (pin "1") (pinfunction "P_1") (pintype "passive"))
    )
    (net (code "76") (name "unconnected-(PAD33-P-Pad1)") (class "Default")
      (node (ref "PAD33") (pin "1") (pinfunction "P_1") (pintype "passive"))
    )
    (net (code "77") (name "unconnected-(PAD34-P-Pad1)") (class "Default")
      (node (ref "PAD34") (pin "1") (pinfunction "P_1") (pintype "passive"))
    )
    (net (code "78") (name "unconnected-(PAD35-P-Pad1)") (class "Default")
      (node (ref "PAD35") (pin "1") (pinfunction "P_1") (pintype "passive"))
    )
    (net (code "79") (name "unconnected-(PAD36-P-Pad1)") (class "Default")
      (node (ref "PAD36") (pin "1") (pinfunction "P_1") (pintype "passive"))
    )
    (net (code "80") (name "unconnected-(PAD37-P-Pad1)") (class "Default")
      (node (ref "PAD37") (pin "1") (pinfunction "P_1") (pintype "passive"))
    )
    (net (code "81") (name "unconnected-(PAD38-P-Pad1)") (class "Default")
      (node (ref "PAD38") (pin "1") (pinfunction "P_1") (pintype "passive"))
    )
    (net (code "82") (name "unconnected-(PAD39-P-Pad1)") (class "Default")
      (node (ref "PAD39") (pin "1") (pinfunction "P_1") (pintype "passive"))
    )
    (net (code "83") (name "unconnected-(PAD40-P-Pad1)") (class "Default")
      (node (ref "PAD40") (pin "1") (pinfunction "P_1") (pintype "passive"))
    )
    (net (code "84") (name "unconnected-(PAD41-P-Pad1)") (class "Default")
      (node (ref "PAD41") (pin "1") (pinfunction "P_1") (pintype "passive"))
    )
    (net (code "85") (name "unconnected-(PAD42-P-Pad1)") (class "Default")
      (node (ref "PAD42") (pin "1") (pinfunction "P_1") (pintype "passive"))
    )
    (net (code "86") (name "unconnected-(PAD43-P-Pad1)") (class "Default")
      (node (ref "PAD43") (pin "1") (pinfunction "P_1") (pintype "passive"))
    )
    (net (code "87") (name "unconnected-(PAD44-P-Pad1)") (class "Default")
      (node (ref "PAD44") (pin "1") (pinfunction "P_1") (pintype "passive"))
    )
    (net (code "88") (name "unconnected-(PAD45-P-Pad1)") (class "Default")
      (node (ref "PAD45") (pin "1") (pinfunction "P_1") (pintype "passive"))
    )
    (net (code "89") (name "unconnected-(PAD46-P-Pad1)") (class "Default")
      (node (ref "PAD46") (pin "1") (pinfunction "P_1") (pintype "passive"))
    )
    (net (code "90") (name "unconnected-(PAD47-P-Pad1)") (class "Default")
      (node (ref "PAD47") (pin "1") (pinfunction "P_1") (pintype "passive"))
    )
    (net (code "91") (name "unconnected-(PAD48-P-Pad1)") (class "Default")
      (node (ref "PAD48") (pin "1") (pinfunction "P_1") (pintype "passive"))
    )
    (net (code "92") (name "unconnected-(PAD49-P-Pad1)") (class "Default")
      (node (ref "PAD49") (pin "1") (pinfunction "P_1") (pintype "passive"))
    )
    (net (code "93") (name "unconnected-(PAD50-P-Pad1)") (class "Default")
      (node (ref "PAD50") (pin "1") (pinfunction "P_1") (pintype "passive"))
    )
    (net (code "94") (name "unconnected-(PAD51-P-Pad1)") (class "Default")
      (node (ref "PAD51") (pin "1") (pinfunction "P_1") (pintype "passive"))
    )
    (net (code "95") (name "unconnected-(PAD52-P-Pad1)") (class "Default")
      (node (ref "PAD52") (pin "1") (pinfunction "P_1") (pintype "passive"))
    )
    (net (code "96") (name "unconnected-(PAD53-P-Pad1)") (class "Default")
      (node (ref "PAD53") (pin "1") (pinfunction "P_1") (pintype "passive"))
    )
    (net (code "97") (name "unconnected-(PAD54-P-Pad1)") (class "Default")
      (node (ref "PAD54") (pin "1") (pinfunction "P_1") (pintype "passive"))
    )
    (net (code "98") (name "unconnected-(PAD56-P-Pad1)") (class "Default")
      (node (ref "PAD56") (pin "1") (pinfunction "P_1") (pintype "passive"))
    )
    (net (code "99") (name "unconnected-(PAD57-P-Pad1)") (class "Default")
      (node (ref "PAD57") (pin "1") (pinfunction "P_1") (pintype "passive"))
    )
    (net (code "100") (name "unconnected-(PAD58-P-Pad1)") (class "Default")
      (node (ref "PAD58") (pin "1") (pinfunction "P_1") (pintype "passive"))
    )
    (net (code "101") (name "unconnected-(PAD59-P-Pad1)") (class "Default")
      (node (ref "PAD59") (pin "1") (pinfunction "P_1") (pintype "passive"))
    )
    (net (code "102") (name "unconnected-(PAD60-P-Pad1)") (class "Default")
      (node (ref "PAD60") (pin "1") (pinfunction "P_1") (pintype "passive"))
    )
    (net (code "103") (name "unconnected-(PAD61-P-Pad1)") (class "Default")
      (node (ref "PAD61") (pin "1") (pinfunction "P_1") (pintype "passive"))
    )
    (net (code "104") (name "unconnected-(PAD62-P-Pad1)") (class "Default")
      (node (ref "PAD62") (pin "1") (pinfunction "P_1") (pintype "passive"))
    )
    (net (code "105") (name "unconnected-(PAD63-P-Pad1)") (class "Default")
      (node (ref "PAD63") (pin "1") (pinfunction "P_1") (pintype "passive"))
    )
    (net (code "106") (name "unconnected-(PAD64-P-Pad1)") (class "Default")
      (node (ref "PAD64") (pin "1") (pinfunction "P_1") (pintype "passive"))
    )
    (net (code "107") (name "unconnected-(PAD65-P-Pad1)") (class "Default")
      (node (ref "PAD65") (pin "1") (pinfunction "P_1") (pintype "passive"))
    )
    (net (code "108") (name "unconnected-(PAD66-P-Pad1)") (class "Default")
      (node (ref "PAD66") (pin "1") (pinfunction "P_1") (pintype "passive"))
    )
    (net (code "109") (name "unconnected-(PAD67-P-Pad1)") (class "Default")
      (node (ref "PAD67") (pin "1") (pinfunction "P_1") (pintype "passive"))
    )
    (net (code "110") (name "unconnected-(PAD69-P-Pad1)") (class "Default")
      (node (ref "PAD69") (pin "1") (pinfunction "P_1") (pintype "passive"))
    )
    (net (code "111") (name "unconnected-(PAD70-P-Pad1)") (class "Default")
      (node (ref "PAD70") (pin "1") (pinfunction "P_1") (pintype "passive"))
    )
    (net (code "112") (name "unconnected-(PAD71-P-Pad1)") (class "Default")
      (node (ref "PAD71") (pin "1") (pinfunction "P_1") (pintype "passive"))
    )
    (net (code "113") (name "unconnected-(PAD72-P-Pad1)") (class "Default")
      (node (ref "PAD72") (pin "1") (pinfunction "P_1") (pintype "passive"))
    )
    (net (code "114") (name "unconnected-(PAD73-P-Pad1)") (class "Default")
      (node (ref "PAD73") (pin "1") (pinfunction "P_1") (pintype "passive"))
    )
    (net (code "115") (name "unconnected-(PAD74-P-Pad1)") (class "Default")
      (node (ref "PAD74") (pin "1") (pinfunction "P_1") (pintype "passive"))
    )
    (net (code "116") (name "unconnected-(U1-PadA0)") (class "Default")
      (node (ref "U1") (pin "A0") (pinfunction "A0_A0") (pintype "bidirectional"))
    )
    (net (code "117") (name "unconnected-(U1-PadA1)") (class "Default")
      (node (ref "U1") (pin "A1") (pinfunction "A1_A1") (pintype "bidirectional"))
    )
    (net (code "118") (name "unconnected-(U1-PadA2)") (class "Default")
      (node (ref "U1") (pin "A2") (pinfunction "A2_A2") (pintype "bidirectional"))
    )
    (net (code "119") (name "unconnected-(U1-PadA3)") (class "Default")
      (node (ref "U1") (pin "A3") (pinfunction "A3_A3") (pintype "bidirectional"))
    )
    (net (code "120") (name "unconnected-(U1-PadAREF)") (class "Default")
      (node (ref "U1") (pin "AREF") (pinfunction "AREF_AREF") (pintype "bidirectional"))
    )
    (net (code "121") (name "unconnected-(U1-PadD0)") (class "Default")
      (node (ref "U1") (pin "D0") (pinfunction "D0_D0") (pintype "bidirectional"))
    )
    (net (code "122") (name "unconnected-(U1-PadD1)") (class "Default")
      (node (ref "U1") (pin "D1") (pinfunction "D1_D1") (pintype "bidirectional"))
    )
    (net (code "123") (name "unconnected-(U1-PadD2)") (class "Default")
      (node (ref "U1") (pin "D2") (pinfunction "D2_D2") (pintype "bidirectional"))
    )
    (net (code "124") (name "unconnected-(U1-PadD3)") (class "Default")
      (node (ref "U1") (pin "D3") (pinfunction "D3_D3") (pintype "bidirectional"))
    )
    (net (code "125") (name "unconnected-(U1-PadD4)") (class "Default")
      (node (ref "U1") (pin "D4") (pinfunction "D4_D4") (pintype "bidirectional"))
    )
    (net (code "126") (name "unconnected-(U1-PadD5)") (class "Default")
      (node (ref "U1") (pin "D5") (pinfunction "D5_D5") (pintype "bidirectional"))
    )
    (net (code "127") (name "unconnected-(U1-PadD6)") (class "Default")
      (node (ref "U1") (pin "D6") (pinfunction "D6_D6") (pintype "bidirectional"))
    )
    (net (code "128") (name "unconnected-(U1-PadD7)") (class "Default")
      (node (ref "U1") (pin "D7") (pinfunction "D7_D7") (pintype "bidirectional"))
    )
    (net (code "129") (name "unconnected-(U1-PadD8)") (class "Default")
      (node (ref "U1") (pin "D8") (pinfunction "D8_D8") (pintype "bidirectional"))
    )
    (net (code "130") (name "unconnected-(U1-PadD9)") (class "Default")
      (node (ref "U1") (pin "D9") (pinfunction "D9_D9") (pintype "bidirectional"))
    )
    (net (code "131") (name "unconnected-(U1-PadSCL)") (class "Default")
      (node (ref "U1") (pin "SCL") (pinfunction "SCL_SCL") (pintype "bidirectional"))
    )
    (net (code "132") (name "unconnected-(U1-PadSDA)") (class "Default")
      (node (ref "U1") (pin "SDA") (pinfunction "SDA_SDA") (pintype "bidirectional"))
    )
    (net (code "133") (name "unconnected-(U1-{slash}RESET-PadRESET)") (class "Default")
      (node (ref "U1") (pin "RESET") (pinfunction "/RESET_RESET") (pintype "bidirectional"))
    )
  )
)
